# Actuators.net
KiCad netlist of a schematic drawn in Altium Designer
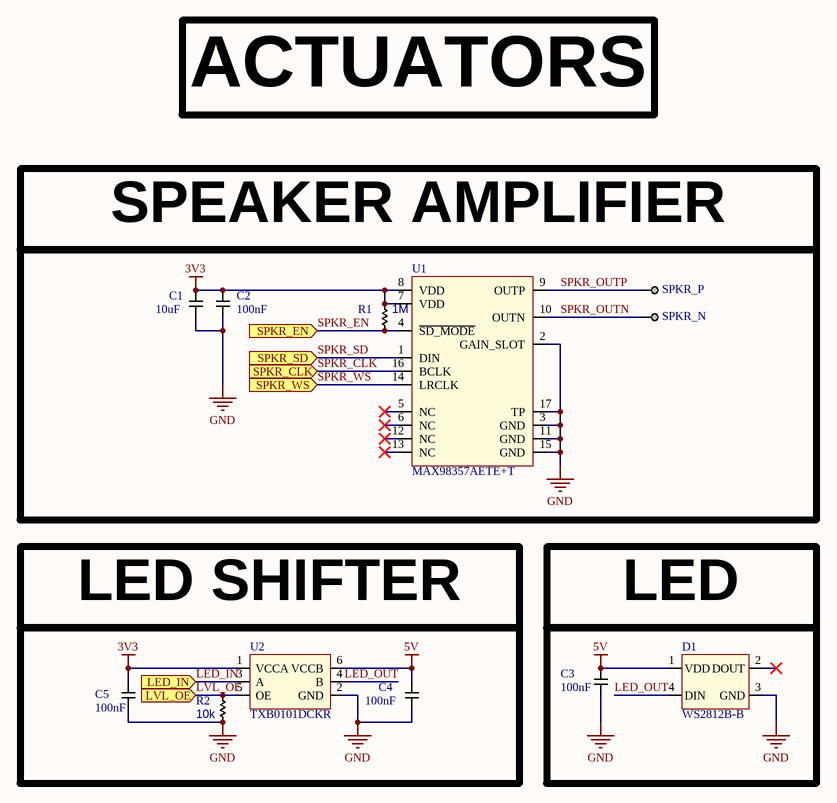
[diagram p0: Actuators.SchDoc]

(export (version "E")
  (design (tool "Eeschema 10.0.6"))
  (components
    (comp (ref "C1")
      (value "10uF")
      (footprint "CAP_0603_HIGH")
      (description "0603 Capacitor")
      (libsource (lib "smLib") (part "Capacitor_0603"))
    )
    (comp (ref "C2")
      (value "100nF")
      (footprint "CAP_0402_HIGH")
      (description "0402 Capacitor")
      (libsource (lib "smLib") (part "Capacitor_0402"))
    )
    (comp (ref "C3")
      (value "100nF")
      (footprint "CAP_0402_HIGH")
      (description "0402 Capacitor")
      (libsource (lib "smLib") (part "Capacitor_0402"))
    )
    (comp (ref "C4")
      (value "100nF")
      (footprint "CAP_0402_HIGH")
      (description "0402 Capacitor")
      (libsource (lib "smLib") (part "Capacitor_0402"))
    )
    (comp (ref "C5")
      (value "100nF")
      (footprint "CAP_0402_HIGH")
      (description "0402 Capacitor")
      (libsource (lib "smLib") (part "Capacitor_0402"))
    )
    (comp (ref "D1") (value "WS2812B-B") (footprint "WS2812B-B") (libsource (lib "smLib") (part "WS2812B-B")))
    (comp (ref "R1")
      (value "1M")
      (footprint "RES_0402_HIGH")
      (description "0402 Resistor")
      (libsource (lib "smLib") (part "Resistor_0402"))
    )
    (comp (ref "R2")
      (value "10k")
      (footprint "RES_0402_HIGH")
      (description "0402 Resistor")
      (libsource (lib "smLib") (part "Resistor_0402"))
    )
    (comp (ref "SPKR_N")
      (value "0.1\" Header")
      (footprint "0.1\" Header")
      (libsource (lib "smLib") (part "0.1{dblquote} Header"))
    )
    (comp (ref "SPKR_P")
      (value "0.1\" Header")
      (footprint "0.1\" Header")
      (libsource (lib "smLib") (part "0.1{dblquote} Header"))
    )
    (comp (ref "U1")
      (value "MAX98357AETE+T")
      (footprint "MAX98357AETE+T")
      (description "MAX98357AETE+T Amplifier IC 1-Channel (Mono) Class D 16-TQFN (3x3)")
      (libsource (lib "smLib") (part "MAX98357AETE+T"))
    )
    (comp (ref "U2")
      (value "TXB0101DCKR")
      (footprint "TXB0101DCKR")
      (description "TXB0101DCKR Voltage Level Translator Bidirectional 1 Circuit 1 Channel 100Mbps SC-70-6")
      (libsource (lib "smLib") (part "TXB0101DCKR"))
    )
  )
  (nets
    (net (code "1") (name "/LED_IN") (class "Default")
      (node (ref "U2") (pin "3") (pinfunction "A_3") (pintype "passive"))
    )
    (net (code "2") (name "/LED_OUT") (class "Default")
      (node (ref "D1") (pin "4") (pinfunction "DIN_4") (pintype "passive"))
      (node (ref "U2") (pin "4") (pinfunction "B_4") (pintype "passive"))
    )
    (net (code "3") (name "/LVL_OE") (class "Default")
      (node (ref "R2") (pin "2") (pinfunction "2_2") (pintype "passive"))
      (node (ref "U2") (pin "5") (pinfunction "OE_5") (pintype "passive"))
    )
    (net (code "4") (name "/SPKR_CLK") (class "Default")
      (node (ref "U1") (pin "16") (pinfunction "BCLK_16") (pintype "passive"))
    )
    (net (code "5") (name "/SPKR_EN") (class "Default")
      (node (ref "R1") (pin "1") (pinfunction "1_1") (pintype "passive"))
      (node (ref "U1") (pin "4") (pinfunction "~{SD_MODE}_4") (pintype "passive"))
    )
    (net (code "6") (name "/SPKR_OUTN") (class "Default")
      (node (ref "SPKR_N") (pin "1") (pinfunction "1_1") (pintype "passive"))
      (node (ref "U1") (pin "10") (pinfunction "OUTN_10") (pintype "passive"))
    )
    (net (code "7") (name "/SPKR_OUTP") (class "Default")
      (node (ref "SPKR_P") (pin "1") (pinfunction "1_1") (pintype "passive"))
      (node (ref "U1") (pin "9") (pinfunction "OUTP_9") (pintype "passive"))
    )
    (net (code "8") (name "/SPKR_SD") (class "Default")
      (node (ref "U1") (pin "1") (pinfunction "DIN_1") (pintype "passive"))
    )
    (net (code "9") (name "/SPKR_WS") (class "Default")
      (node (ref "U1") (pin "14") (pinfunction "LRCLK_14") (pintype "passive"))
    )
    (net (code "10") (name "3V3") (class "Default")
      (node (ref "C1") (pin "2") (pinfunction "2_2") (pintype "passive"))
      (node (ref "C2") (pin "2") (pinfunction "2_2") (pintype "passive"))
      (node (ref "C5") (pin "2") (pinfunction "2_2") (pintype "passive"))
      (node (ref "R1") (pin "2") (pinfunction "2_2") (pintype "passive"))
      (node (ref "U1") (pin "7") (pinfunction "VDD_7") (pintype "passive"))
      (node (ref "U1") (pin "8") (pinfunction "VDD_8") (pintype "passive"))
      (node (ref "U2") (pin "1") (pinfunction "VCCA_1") (pintype "passive"))
    )
    (net (code "11") (name "5V") (class "Default")
      (node (ref "C3") (pin "2") (pinfunction "2_2") (pintype "passive"))
      (node (ref "C4") (pin "2") (pinfunction "2_2") (pintype "passive"))
      (node (ref "D1") (pin "1") (pinfunction "VDD_1") (pintype "passive"))
      (node (ref "U2") (pin "6") (pinfunction "VCCB_6") (pintype "passive"))
    )
    (net (code "12") (name "GND") (class "Default")
      (node (ref "C1") (pin "1") (pinfunction "1_1") (pintype "passive"))
      (node (ref "C2") (pin "1") (pinfunction "1_1") (pintype "passive"))
      (node (ref "C3") (pin "1") (pinfunction "1_1") (pintype "passive"))
      (node (ref "C4") (pin "1") (pinfunction "1_1") (pintype "passive"))
      (node (ref "C5") (pin "1") (pinfunction "1_1") (pintype "passive"))
      (node (ref "D1") (pin "3") (pinfunction "GND_3") (pintype "passive"))
      (node (ref "R2") (pin "1") (pinfunction "1_1") (pintype "passive"))
      (node (ref "U1") (pin "11") (pinfunction "GND_11") (pintype "passive"))
      (node (ref "U1") (pin "15") (pinfunction "GND_15") (pintype "passive"))
      (node (ref "U1") (pin "17") (pinfunction "TP_17") (pintype "passive"))
      (node (ref "U1") (pin "2") (pinfunction "GAIN_SLOT_2") (pintype "passive"))
      (node (ref "U1") (pin "3") (pinfunction "GND_3") (pintype "passive"))
      (node (ref "U2") (pin "2") (pinfunction "GND_2") (pintype "passive"))
    )
    (net (code "13") (name "unconnected-(D1-DOUT-Pad2)") (class "Default")
      (node (ref "D1") (pin "2") (pinfunction "DOUT_2") (pintype "passive+no_connect"))
    )
    (net (code "14") (name "unconnected-(U1-NC-Pad5)") (class "Default")
      (node (ref "U1") (pin "5") (pinfunction "NC_5") (pintype "passive+no_connect"))
    )
    (net (code "15") (name "unconnected-(U1-NC-Pad6)") (class "Default")
      (node (ref "U1") (pin "6") (pinfunction "NC_6") (pintype "passive+no_connect"))
    )
    (net (code "16") (name "unconnected-(U1-NC-Pad12)") (class "Default")
      (node (ref "U1") (pin "12") (pinfunction "NC_12") (pintype "passive+no_connect"))
    )
    (net (code "17") (name "unconnected-(U1-NC-Pad13)") (class "Default")
      (node (ref "U1") (pin "13") (pinfunction "NC_13") (pintype "passive+no_connect"))
    )
  )
)
